# Temperature.net
KiCad netlist of a schematic drawn in EAGLE
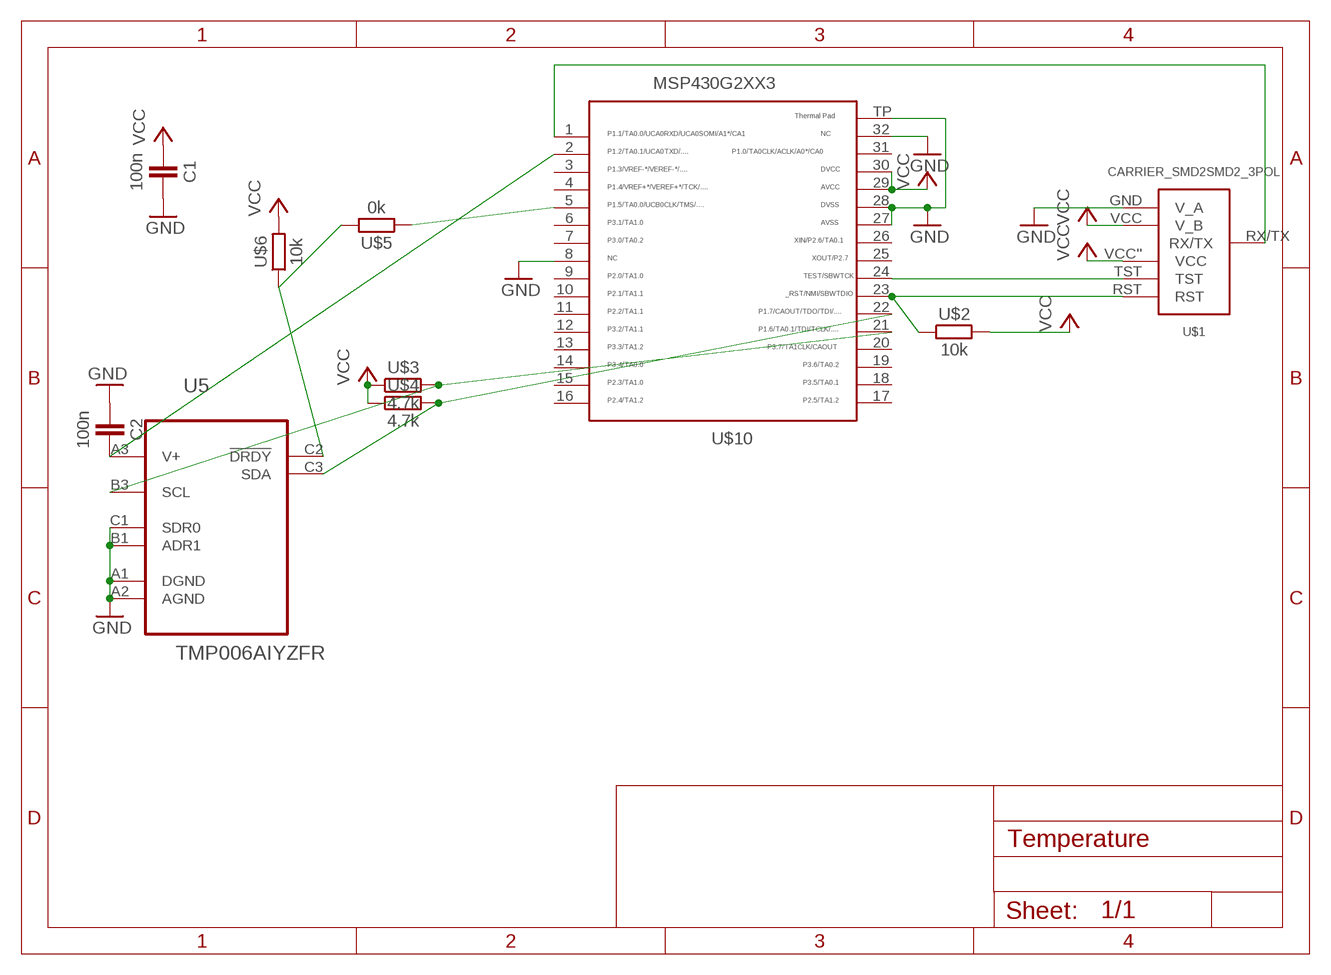
[diagram p0: schematic, sheet 1]

(export (version "E")
  (design (tool "Eeschema 10.0.6"))
  (components
    (comp (ref "C1")
      (value "100n")
      (footprint "eagle-import:603")
      (libsource (lib "eagle-import") (part "CAPACITOR"))
    )
    (comp (ref "C2")
      (value "100n")
      (footprint "eagle-import:603")
      (libsource (lib "eagle-import") (part "CAPACITOR"))
    )
    (comp (ref "U$1")
      (value "CARRIER_SMD2SMD2_3POL")
      (footprint "eagle-import:CARRIER_SMD2_3POL")
      (libsource (lib "eagle-import") (part "CARRIER_SMD2SMD2_3POL"))
    )
    (comp (ref "U$2")
      (value "10k")
      (footprint "eagle-import:603")
      (libsource (lib "eagle-import") (part "RESISTOR0603"))
    )
    (comp (ref "U$3")
      (value "4.7k")
      (footprint "eagle-import:603")
      (libsource (lib "eagle-import") (part "RESISTOR0603"))
    )
    (comp (ref "U$4")
      (value "4.7k")
      (footprint "eagle-import:603")
      (libsource (lib "eagle-import") (part "RESISTOR0603"))
    )
    (comp (ref "U$5")
      (value "0k")
      (footprint "eagle-import:1206")
      (libsource (lib "eagle-import") (part "RESISTOR1206"))
    )
    (comp (ref "U$6")
      (value "10k")
      (footprint "eagle-import:603")
      (libsource (lib "eagle-import") (part "RESISTOR0603"))
    )
    (comp (ref "U$10")
      (value "MSP430G2553")
      (footprint "eagle-import:QFN32")
      (libsource (lib "eagle-import") (part "MSP430G2553"))
    )
    (comp (ref "U5")
      (value "TMP006AIYZFR")
      (footprint "eagle-import:BGA8C50P3X3_156X156X63")
      (fields (field (name "MPN") "TMP006AIYZFR "))
      (libsource (lib "eagle-import") (part "TMP006AIYZFR"))
    )
  )
  (nets
    (net (code "1") (name "GND") (class "Default")
      (node (ref "C1") (pin "2") (pinfunction "2_2") (pintype "passive"))
      (node (ref "C2") (pin "1") (pinfunction "1_1") (pintype "passive"))
      (node (ref "U$1") (pin "GND") (pinfunction "V_A_GND") (pintype "bidirectional"))
      (node (ref "U$10") (pin "27") (pinfunction "27_27") (pintype "bidirectional"))
      (node (ref "U$10") (pin "28") (pinfunction "28_28") (pintype "bidirectional"))
      (node (ref "U$10") (pin "32") (pinfunction "32_32") (pintype "bidirectional"))
      (node (ref "U$10") (pin "8") (pinfunction "8_8") (pintype "bidirectional"))
      (node (ref "U$10") (pin "TP") (pinfunction "TP_TP") (pintype "bidirectional"))
      (node (ref "U5") (pin "A1") (pinfunction "DGND_A1") (pintype "passive"))
      (node (ref "U5") (pin "A2") (pinfunction "AGND_A2") (pintype "passive"))
      (node (ref "U5") (pin "B1") (pinfunction "ADR1_B1") (pintype "input"))
      (node (ref "U5") (pin "C1") (pinfunction "SDR0_C1") (pintype "passive"))
    )
    (net (code "2") (name "Net-(U$1-PadRST)") (class "Default")
      (node (ref "U$1") (pin "RST") (pinfunction "RST_RST") (pintype "bidirectional"))
      (node (ref "U$10") (pin "23") (pinfunction "23_23") (pintype "bidirectional"))
      (node (ref "U$2") (pin "1") (pinfunction "1_1") (pintype "passive"))
    )
    (net (code "3") (name "Net-(U$1-PadRX{slash}TX)") (class "Default")
      (node (ref "U$1") (pin "RX/TX") (pinfunction "RX/TX_RX/TX") (pintype "bidirectional"))
      (node (ref "U$10") (pin "1") (pinfunction "1_1") (pintype "bidirectional"))
    )
    (net (code "4") (name "Net-(U$1-PadTST)") (class "Default")
      (node (ref "U$1") (pin "TST") (pinfunction "TST_TST") (pintype "bidirectional"))
      (node (ref "U$10") (pin "24") (pinfunction "24_24") (pintype "bidirectional"))
    )
    (net (code "5") (name "Net-(U$10-Pad5)") (class "Default")
      (node (ref "U$10") (pin "5") (pinfunction "5_5") (pintype "bidirectional"))
      (node (ref "U$5") (pin "1") (pinfunction "1_1") (pintype "passive"))
    )
    (net (code "6") (name "Net-(U5-SCL)") (class "Default")
      (node (ref "U$10") (pin "21") (pinfunction "21_21") (pintype "bidirectional"))
      (node (ref "U$3") (pin "2") (pinfunction "2_2") (pintype "passive"))
      (node (ref "U5") (pin "B3") (pinfunction "SCL_B3") (pintype "input"))
    )
    (net (code "7") (name "Net-(U5-SDA)") (class "Default")
      (node (ref "U$10") (pin "22") (pinfunction "22_22") (pintype "bidirectional"))
      (node (ref "U$4") (pin "2") (pinfunction "2_2") (pintype "passive"))
      (node (ref "U5") (pin "C3") (pinfunction "SDA_C3") (pintype "bidirectional"))
    )
    (net (code "8") (name "Net-(U5-V+)") (class "Default")
      (node (ref "C2") (pin "2") (pinfunction "2_2") (pintype "passive"))
      (node (ref "U$10") (pin "2") (pinfunction "2_2") (pintype "bidirectional"))
      (node (ref "U5") (pin "A3") (pinfunction "V+_A3") (pintype "power_in"))
    )
    (net (code "9") (name "Net-(U5-~{DRDY})") (class "Default")
      (node (ref "U$5") (pin "2") (pinfunction "2_2") (pintype "passive"))
      (node (ref "U$6") (pin "1") (pinfunction "1_1") (pintype "passive"))
      (node (ref "U5") (pin "C2") (pinfunction "~{DRDY}_C2") (pintype "passive"))
    )
    (net (code "10") (name "VCC") (class "Default")
      (node (ref "C1") (pin "1") (pinfunction "1_1") (pintype "passive"))
      (node (ref "U$1") (pin "VCC") (pinfunction "V_B_VCC") (pintype "bidirectional"))
      (node (ref "U$1") (pin "VCC''") (pinfunction "VCC_VCC''") (pintype "bidirectional"))
      (node (ref "U$10") (pin "29") (pinfunction "29_29") (pintype "bidirectional"))
      (node (ref "U$10") (pin "30") (pinfunction "30_30") (pintype "bidirectional"))
      (node (ref "U$2") (pin "2") (pinfunction "2_2") (pintype "passive"))
      (node (ref "U$3") (pin "1") (pinfunction "1_1") (pintype "passive"))
      (node (ref "U$4") (pin "1") (pinfunction "1_1") (pintype "passive"))
      (node (ref "U$6") (pin "2") (pinfunction "2_2") (pintype "passive"))
    )
    (net (code "11") (name "unconnected-(U$10-Pad3)") (class "Default")
      (node (ref "U$10") (pin "3") (pinfunction "3_3") (pintype "bidirectional"))
    )
    (net (code "12") (name "unconnected-(U$10-Pad4)") (class "Default")
      (node (ref "U$10") (pin "4") (pinfunction "4_4") (pintype "bidirectional"))
    )
    (net (code "13") (name "unconnected-(U$10-Pad6)") (class "Default")
      (node (ref "U$10") (pin "6") (pinfunction "6_6") (pintype "bidirectional"))
    )
    (net (code "14") (name "unconnected-(U$10-Pad7)") (class "Default")
      (node (ref "U$10") (pin "7") (pinfunction "7_7") (pintype "bidirectional"))
    )
    (net (code "15") (name "unconnected-(U$10-Pad9)") (class "Default")
      (node (ref "U$10") (pin "9") (pinfunction "9_9") (pintype "bidirectional"))
    )
    (net (code "16") (name "unconnected-(U$10-Pad10)") (class "Default")
      (node (ref "U$10") (pin "10") (pinfunction "10_10") (pintype "bidirectional"))
    )
    (net (code "17") (name "unconnected-(U$10-Pad11)") (class "Default")
      (node (ref "U$10") (pin "11") (pinfunction "11_11") (pintype "bidirectional"))
    )
    (net (code "18") (name "unconnected-(U$10-Pad12)") (class "Default")
      (node (ref "U$10") (pin "12") (pinfunction "12_12") (pintype "bidirectional"))
    )
    (net (code "19") (name "unconnected-(U$10-Pad13)") (class "Default")
      (node (ref "U$10") (pin "13") (pinfunction "13_13") (pintype "bidirectional"))
    )
    (net (code "20") (name "unconnected-(U$10-Pad14)") (class "Default")
      (node (ref "U$10") (pin "14") (pinfunction "14_14") (pintype "bidirectional"))
    )
    (net (code "21") (name "unconnected-(U$10-Pad15)") (class "Default")
      (node (ref "U$10") (pin "15") (pinfunction "15_15") (pintype "bidirectional"))
    )
    (net (code "22") (name "unconnected-(U$10-Pad16)") (class "Default")
      (node (ref "U$10") (pin "16") (pinfunction "16_16") (pintype "bidirectional"))
    )
    (net (code "23") (name "unconnected-(U$10-Pad17)") (class "Default")
      (node (ref "U$10") (pin "17") (pinfunction "17_17") (pintype "bidirectional"))
    )
    (net (code "24") (name "unconnected-(U$10-Pad18)") (class "Default")
      (node (ref "U$10") (pin "18") (pinfunction "18_18") (pintype "bidirectional"))
    )
    (net (code "25") (name "unconnected-(U$10-Pad19)") (class "Default")
      (node (ref "U$10") (pin "19") (pinfunction "19_19") (pintype "bidirectional"))
    )
    (net (code "26") (name "unconnected-(U$10-Pad20)") (class "Default")
      (node (ref "U$10") (pin "20") (pinfunction "20_20") (pintype "bidirectional"))
    )
    (net (code "27") (name "unconnected-(U$10-Pad25)") (class "Default")
      (node (ref "U$10") (pin "25") (pinfunction "25_25") (pintype "bidirectional"))
    )
    (net (code "28") (name "unconnected-(U$10-Pad26)") (class "Default")
      (node (ref "U$10") (pin "26") (pinfunction "26_26") (pintype "bidirectional"))
    )
    (net (code "29") (name "unconnected-(U$10-Pad31)") (class "Default")
      (node (ref "U$10") (pin "31") (pinfunction "31_31") (pintype "bidirectional"))
    )
  )
)
